# Transist_rle_Led_Kontrol_Devresi.net
KiCad netlist of a schematic drawn in EasyEDA Pro
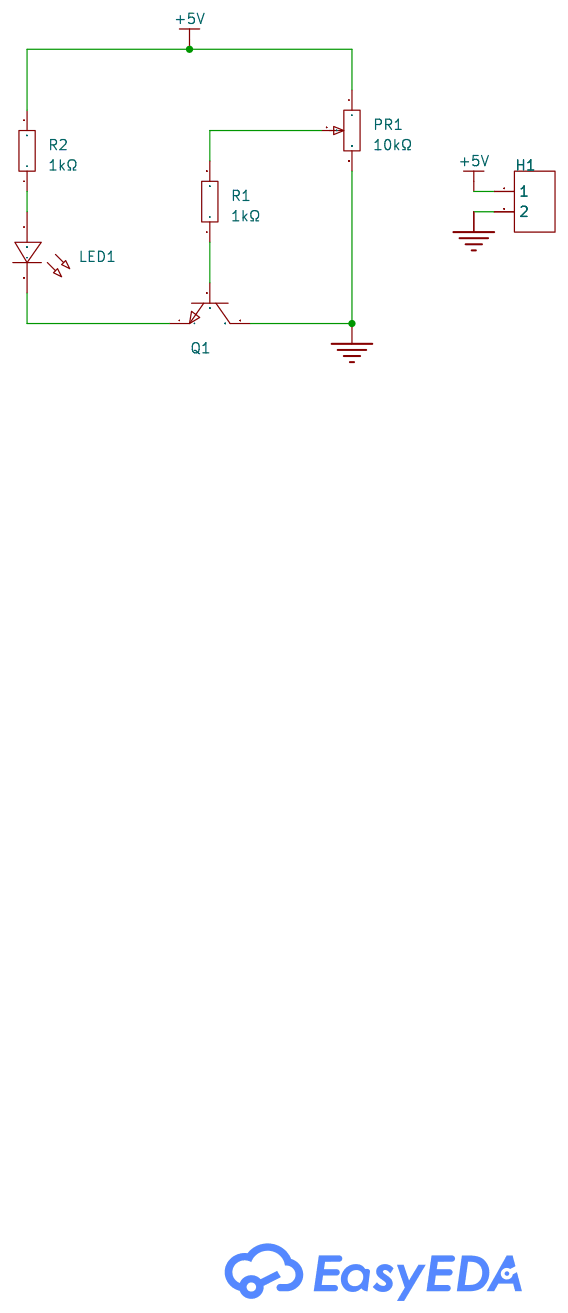
[diagram p0: schematic sheet]

(export (version "E")
  (design (tool "Eeschema 10.0.6"))
  (components
    (comp (ref "H1")
      (value "~")
      (footprint "easyedapro:HDR-TH_2P-P2.54-V-F")
      (fields (field (name "Manufacturer Part") "2.54-1*2P母") (field (name "Manufacturer") "BOOMELE(博穆精密)"))
      (libsource (lib "easyedapro") (part "Header-Female-2.54_1x2"))
    )
    (comp (ref "LED1")
      (value "~")
      (footprint "easyedapro:LED_TH-3mm")
      (libsource (lib "easyedapro") (part "LED_TH-R"))
    )
    (comp (ref "PR1")
      (value "10kΩ")
      (footprint "easyedapro:R_3296")
      (libsource (lib "easyedapro") (part "R_3296"))
    )
    (comp (ref "Q1")
      (value "~")
      (footprint "easyedapro:S8050_TO_92")
      (libsource (lib "easyedapro") (part "S8050_TO_NPN"))
    )
    (comp (ref "R1")
      (value "1kΩ")
      (footprint "easyedapro:Res_1/4W")
      (libsource (lib "easyedapro") (part "电阻"))
    )
    (comp (ref "R2")
      (value "1kΩ")
      (footprint "easyedapro:Res_1/4W")
      (libsource (lib "easyedapro") (part "电阻"))
    )
  )
  (nets
    (net (code "1") (name "+5V") (class "Default")
      (node (ref "H1") (pin "1") (pinfunction "1_1") (pintype "input"))
      (node (ref "PR1") (pin "1") (pinfunction "1_1") (pintype "input"))
      (node (ref "R2") (pin "2") (pinfunction "2_2") (pintype "input"))
    )
    (net (code "2") (name "GND") (class "Default")
      (node (ref "H1") (pin "2") (pinfunction "2_2") (pintype "input"))
      (node (ref "PR1") (pin "3") (pinfunction "3_3") (pintype "input"))
      (node (ref "Q1") (pin "3") (pinfunction "C_3") (pintype "unspecified"))
    )
    (net (code "3") (name "Net-(LED1-A)") (class "Default")
      (node (ref "LED1") (pin "2") (pinfunction "A_2") (pintype "input"))
      (node (ref "Q1") (pin "1") (pinfunction "E_1") (pintype "unspecified"))
    )
    (net (code "4") (name "Net-(LED1-C)") (class "Default")
      (node (ref "LED1") (pin "1") (pinfunction "C_1") (pintype "input"))
      (node (ref "R2") (pin "1") (pinfunction "1_1") (pintype "input"))
    )
    (net (code "5") (name "Net-(PR1-Pad2)") (class "Default")
      (node (ref "PR1") (pin "2") (pinfunction "2_2") (pintype "input"))
      (node (ref "R1") (pin "2") (pinfunction "2_2") (pintype "input"))
    )
    (net (code "6") (name "Net-(Q1-B)") (class "Default")
      (node (ref "Q1") (pin "2") (pinfunction "B_2") (pintype "unspecified"))
      (node (ref "R1") (pin "1") (pinfunction "1_1") (pintype "input"))
    )
  )
)
